# Schematic_OpenBook.net
KiCad netlist of a schematic drawn in EAGLE
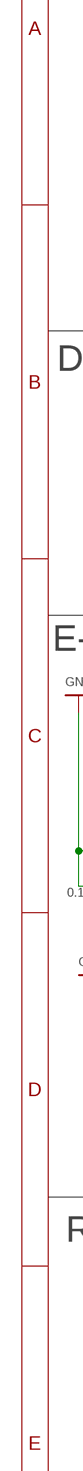
[diagram p0: schematic, sheet 1, part 1 of 2]
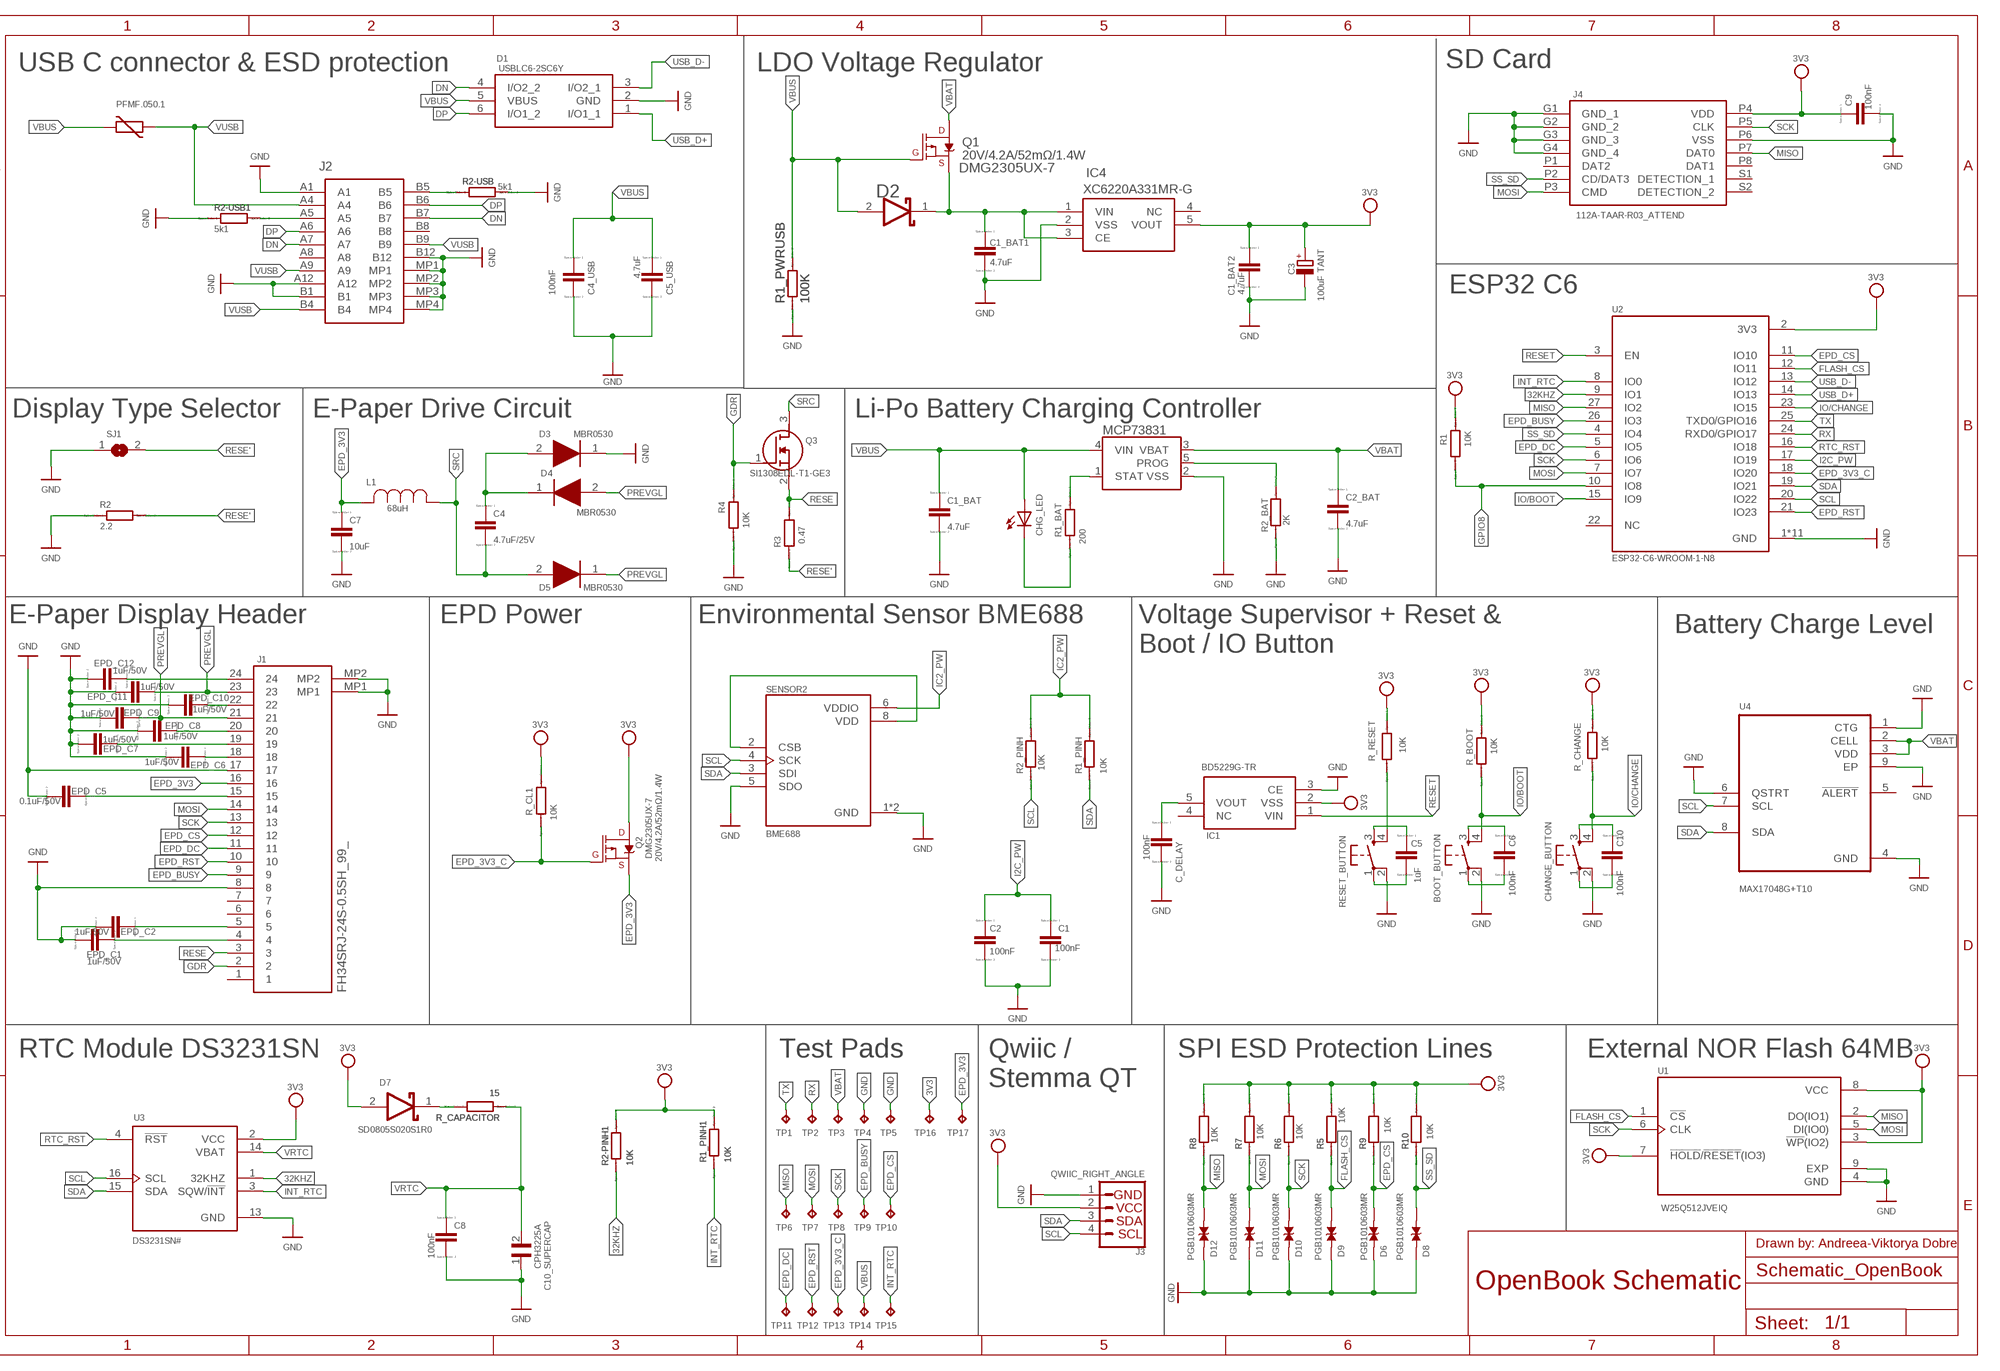
[diagram p1: schematic, sheet 1, part 2 of 2]

(export (version "E")
  (design (tool "Eeschema 10.0.6"))
  (components
    (comp (ref "BOOT_BUTTON")
      (value "BUTTON_CUSYOMV1")
      (footprint "eagle-import:MYBUTTON")
      (libsource (lib "eagle-import") (part "BUTTON_CUSYOMV1"))
    )
    (comp (ref "C1")
      (value "100nF")
      (footprint "eagle-import:ESP32_WROVER_EAGLE-LTSPICE_C0402")
      (libsource (lib "eagle-import") (part "ESP32_WROVER_EAGLE-LTSPICE_CC0402"))
    )
    (comp (ref "C1_BAT")
      (value "4.7uF")
      (footprint "eagle-import:ESP32_WROVER_EAGLE-LTSPICE_C0402")
      (libsource (lib "eagle-import") (part "ESP32_WROVER_EAGLE-LTSPICE_CC0402"))
    )
    (comp (ref "C1_BAT1")
      (value "4.7uF")
      (footprint "eagle-import:ESP32_WROVER_EAGLE-LTSPICE_C0402")
      (libsource (lib "eagle-import") (part "ESP32_WROVER_EAGLE-LTSPICE_CC0402"))
    )
    (comp (ref "C1_BAT2")
      (value "4.7uF")
      (footprint "eagle-import:ESP32_WROVER_EAGLE-LTSPICE_C0402")
      (libsource (lib "eagle-import") (part "ESP32_WROVER_EAGLE-LTSPICE_CC0402"))
    )
    (comp (ref "C2")
      (value "100nF")
      (footprint "eagle-import:ESP32_WROVER_EAGLE-LTSPICE_C0402")
      (libsource (lib "eagle-import") (part "ESP32_WROVER_EAGLE-LTSPICE_CC0402"))
    )
    (comp (ref "C2_BAT")
      (value "4.7uF")
      (footprint "eagle-import:ESP32_WROVER_EAGLE-LTSPICE_C0402")
      (libsource (lib "eagle-import") (part "ESP32_WROVER_EAGLE-LTSPICE_CC0402"))
    )
    (comp (ref "C3")
      (value "100uF TANT")
      (footprint "eagle-import:RCL_CT3528")
      (libsource (lib "eagle-import") (part "RCL_CPOL-EUCT3528"))
    )
    (comp (ref "C4")
      (value "4.7uF/25V")
      (footprint "eagle-import:ESP32_WROVER_EAGLE-LTSPICE_C0402")
      (libsource (lib "eagle-import") (part "ESP32_WROVER_EAGLE-LTSPICE_CC0402"))
    )
    (comp (ref "C4_USB")
      (value "100nF")
      (footprint "eagle-import:ESP32_WROVER_EAGLE-LTSPICE_C0402")
      (libsource (lib "eagle-import") (part "ESP32_WROVER_EAGLE-LTSPICE_CC0402"))
    )
    (comp (ref "C5")
      (value "1uF")
      (footprint "eagle-import:ESP32_WROVER_EAGLE-LTSPICE_C0402")
      (libsource (lib "eagle-import") (part "ESP32_WROVER_EAGLE-LTSPICE_CC0402"))
    )
    (comp (ref "C5_USB")
      (value "4.7uF")
      (footprint "eagle-import:ESP32_WROVER_EAGLE-LTSPICE_C0402")
      (libsource (lib "eagle-import") (part "ESP32_WROVER_EAGLE-LTSPICE_CC0402"))
    )
    (comp (ref "C6")
      (value "100nF")
      (footprint "eagle-import:ESP32_WROVER_EAGLE-LTSPICE_C0402")
      (libsource (lib "eagle-import") (part "ESP32_WROVER_EAGLE-LTSPICE_CC0402"))
    )
    (comp (ref "C7")
      (value "10uF")
      (footprint "eagle-import:ESP32_WROVER_EAGLE-LTSPICE_C0402")
      (libsource (lib "eagle-import") (part "ESP32_WROVER_EAGLE-LTSPICE_CC0402"))
    )
    (comp (ref "C8")
      (value "100nF")
      (footprint "eagle-import:ESP32_WROVER_EAGLE-LTSPICE_C0402")
      (libsource (lib "eagle-import") (part "ESP32_WROVER_EAGLE-LTSPICE_CC0402"))
    )
    (comp (ref "C9")
      (value "100nF")
      (footprint "eagle-import:ESP32_WROVER_EAGLE-LTSPICE_C0402")
      (libsource (lib "eagle-import") (part "ESP32_WROVER_EAGLE-LTSPICE_CC0402"))
    )
    (comp (ref "C10")
      (value "100nF")
      (footprint "eagle-import:ESP32_WROVER_EAGLE-LTSPICE_C0402")
      (libsource (lib "eagle-import") (part "ESP32_WROVER_EAGLE-LTSPICE_CC0402"))
    )
    (comp (ref "C10_SUPERCAP")
      (value "CPH3225A")
      (footprint "eagle-import:CAPCP3225X100N")
      (fields (field (name "MF") "Seiko Instruments"))
      (libsource (lib "eagle-import") (part "CPH3225A"))
    )
    (comp (ref "CHANGE_BUTTON")
      (value "BUTTON_CUSYOMV1")
      (footprint "eagle-import:MYBUTTON")
      (libsource (lib "eagle-import") (part "BUTTON_CUSYOMV1"))
    )
    (comp (ref "CHG_LED")
      (value "ADAFRUIT_LEDCHIP-LED0603")
      (footprint "eagle-import:ADAFRUIT_CHIP-LED0603")
      (libsource (lib "eagle-import") (part "ADAFRUIT_LEDCHIP-LED0603"))
    )
    (comp (ref "C_DELAY")
      (value "100nF")
      (footprint "eagle-import:ESP32_WROVER_EAGLE-LTSPICE_C0402")
      (libsource (lib "eagle-import") (part "ESP32_WROVER_EAGLE-LTSPICE_CC0402"))
    )
    (comp (ref "D1")
      (value "USBLC6-2SC6Y")
      (footprint "eagle-import:SOT95P280X145-6N")
      (fields (field (name "MF") "STMicroelectronics"))
      (libsource (lib "eagle-import") (part "USBLC6-2SC6Y"))
    )
    (comp (ref "D2")
      (value "ESP32_WROVER_AVX---SD0805S020S1R0_AVX_SD0805S020S1R0_0_0AVX_SD0805S020S1R0_0_0")
      (footprint "eagle-import:ESP32_WROVER_AVX---SD0805S020S1R0_AVX_SD0805S020S1R0_0")
      (fields
        (field (name "DIGIKEY_PART_NUMBER") "478-7800-1-ND")
        (field (name "MF") "AVX")
        (field (name "MOUSER_PART_NUMBER") "581-SD0805S020S1R0")
      )
      (libsource (lib "eagle-import") (part "ESP32_WROVER_AVX---SD0805S020S1R0_AVX_SD0805S020S1R0_0_0AVX_SD0805S020S1R0_0_0"))
    )
    (comp (ref "D3")
      (value "MBR0530")
      (footprint "eagle-import:SOD3716X135N")
      (fields (field (name "MF") "ON Semiconductor"))
      (libsource (lib "eagle-import") (part "MBR0530"))
    )
    (comp (ref "D4")
      (value "MBR0530")
      (footprint "eagle-import:SOD3716X135N")
      (fields (field (name "MF") "ON Semiconductor"))
      (libsource (lib "eagle-import") (part "MBR0530"))
    )
    (comp (ref "D5")
      (value "MBR0530")
      (footprint "eagle-import:SOD3716X135N")
      (fields (field (name "MF") "ON Semiconductor"))
      (libsource (lib "eagle-import") (part "MBR0530"))
    )
    (comp (ref "D6")
      (value "PGB1010603MR")
      (footprint "eagle-import:DIOC1608X36N")
      (fields (field (name "MF") "Littelfuse Inc."))
      (libsource (lib "eagle-import") (part "PGB1010603MR"))
    )
    (comp (ref "D7")
      (value "ESP32_WROVER_AVX---SD0805S020S1R0_AVX_SD0805S020S1R0_0_0AVX_SD0805S020S1R0_0_0")
      (footprint "eagle-import:ESP32_WROVER_AVX---SD0805S020S1R0_AVX_SD0805S020S1R0_0")
      (fields
        (field (name "DIGIKEY_PART_NUMBER") "478-7800-1-ND")
        (field (name "MF") "AVX")
        (field (name "MOUSER_PART_NUMBER") "581-SD0805S020S1R0")
      )
      (libsource (lib "eagle-import") (part "ESP32_WROVER_AVX---SD0805S020S1R0_AVX_SD0805S020S1R0_0_0AVX_SD0805S020S1R0_0_0"))
    )
    (comp (ref "D8")
      (value "PGB1010603MR")
      (footprint "eagle-import:DIOC1608X36N")
      (fields (field (name "MF") "Littelfuse Inc."))
      (libsource (lib "eagle-import") (part "PGB1010603MR"))
    )
    (comp (ref "D9")
      (value "PGB1010603MR")
      (footprint "eagle-import:DIOC1608X36N")
      (fields (field (name "MF") "Littelfuse Inc."))
      (libsource (lib "eagle-import") (part "PGB1010603MR"))
    )
    (comp (ref "D10")
      (value "PGB1010603MR")
      (footprint "eagle-import:DIOC1608X36N")
      (fields (field (name "MF") "Littelfuse Inc."))
      (libsource (lib "eagle-import") (part "PGB1010603MR"))
    )
    (comp (ref "D11")
      (value "PGB1010603MR")
      (footprint "eagle-import:DIOC1608X36N")
      (fields (field (name "MF") "Littelfuse Inc."))
      (libsource (lib "eagle-import") (part "PGB1010603MR"))
    )
    (comp (ref "D12")
      (value "PGB1010603MR")
      (footprint "eagle-import:DIOC1608X36N")
      (fields (field (name "MF") "Littelfuse Inc."))
      (libsource (lib "eagle-import") (part "PGB1010603MR"))
    )
    (comp (ref "EPD_C1")
      (value "1uF/50V")
      (footprint "eagle-import:ESP32_WROVER_EAGLE-LTSPICE_C0402")
      (libsource (lib "eagle-import") (part "ESP32_WROVER_EAGLE-LTSPICE_CC0402"))
    )
    (comp (ref "EPD_C2")
      (value "1uF/50V")
      (footprint "eagle-import:ESP32_WROVER_EAGLE-LTSPICE_C0402")
      (libsource (lib "eagle-import") (part "ESP32_WROVER_EAGLE-LTSPICE_CC0402"))
    )
    (comp (ref "EPD_C5")
      (value "0.1uF/50V")
      (footprint "eagle-import:ESP32_WROVER_EAGLE-LTSPICE_C0402")
      (libsource (lib "eagle-import") (part "ESP32_WROVER_EAGLE-LTSPICE_CC0402"))
    )
    (comp (ref "EPD_C6")
      (value "1uF/50V")
      (footprint "eagle-import:ESP32_WROVER_EAGLE-LTSPICE_C0402")
      (libsource (lib "eagle-import") (part "ESP32_WROVER_EAGLE-LTSPICE_CC0402"))
    )
    (comp (ref "EPD_C7")
      (value "1uF/50V")
      (footprint "eagle-import:ESP32_WROVER_EAGLE-LTSPICE_C0402")
      (libsource (lib "eagle-import") (part "ESP32_WROVER_EAGLE-LTSPICE_CC0402"))
    )
    (comp (ref "EPD_C8")
      (value "1uF/50V")
      (footprint "eagle-import:ESP32_WROVER_EAGLE-LTSPICE_C0402")
      (libsource (lib "eagle-import") (part "ESP32_WROVER_EAGLE-LTSPICE_CC0402"))
    )
    (comp (ref "EPD_C9")
      (value "1uF/50V")
      (footprint "eagle-import:ESP32_WROVER_EAGLE-LTSPICE_C0402")
      (libsource (lib "eagle-import") (part "ESP32_WROVER_EAGLE-LTSPICE_CC0402"))
    )
    (comp (ref "EPD_C10")
      (value "1uF/50V")
      (footprint "eagle-import:ESP32_WROVER_EAGLE-LTSPICE_C0402")
      (libsource (lib "eagle-import") (part "ESP32_WROVER_EAGLE-LTSPICE_CC0402"))
    )
    (comp (ref "EPD_C11")
      (value "1uF/50V")
      (footprint "eagle-import:ESP32_WROVER_EAGLE-LTSPICE_C0402")
      (libsource (lib "eagle-import") (part "ESP32_WROVER_EAGLE-LTSPICE_CC0402"))
    )
    (comp (ref "EPD_C12")
      (value "1uF/50V")
      (footprint "eagle-import:ESP32_WROVER_EAGLE-LTSPICE_C0402")
      (libsource (lib "eagle-import") (part "ESP32_WROVER_EAGLE-LTSPICE_CC0402"))
    )
    (comp (ref "IC1")
      (value "XC6220A331MR-G")
      (footprint "eagle-import:SOT95P280X120-5N")
      (fields
        (field (name "MANUFACTURER_PART_NUMBER") "XC6220A331MR-G")
        (field (name "MOUSER_PART_NUMBER") "865-XC6220A331MR-G")
        (field (name "MANUFACTURER_PART_NUMBER_1") "BD5229G-TR")
      )
      (libsource (lib "eagle-import") (part "XC6220A331MR-G"))
    )
    (comp (ref "IC4")
      (value "XC6220A331MR-G")
      (footprint "eagle-import:SOT95P280X120-5N")
      (fields (field (name "MOUSER_PART_NUMBER") "865-XC6220A331MR-G"))
      (libsource (lib "eagle-import") (part "XC6220A331MR-G"))
    )
    (comp (ref "J1")
      (value "FH34SRJ-24S-0.5SH_99_")
      (footprint "eagle-import:FH34SRJ24S05SH99")
      (fields
        (field (name "MANUFACTURER_PART_NUMBER") "FH34SRJ-24S-0.5SH(99)")
        (field (name "MOUSER_PART_NUMBER") "798-FH34SRJ24S05SH99")
      )
      (libsource (lib "eagle-import") (part "FH34SRJ-24S-0.5SH_99_"))
    )
    (comp (ref "J2")
      (value "SAMACSYS_PARTS_USB4110-GF-A")
      (footprint "eagle-import:SAMACSYS_PARTS_USB4110GFA")
      (fields
        (field (name "MANUFACTURER_PART_NUMBER") "USB4110-GF-A")
        (field (name "MOUSER_PART_NUMBER") "640-USB4110-GF-A")
      )
      (libsource (lib "eagle-import") (part "SAMACSYS_PARTS_USB4110-GF-A"))
    )
    (comp (ref "J3")
      (value "QWIIC_RIGHT_ANGLE")
      (footprint "eagle-import:JST04_1MM_RA")
      (libsource (lib "eagle-import") (part "QWIIC_CONNECTORJS-1MM"))
    )
    (comp (ref "J4")
      (value "112A-TAAR-R03_ATTEND")
      (footprint "eagle-import:112ATAARR03ATTEND")
      (fields (field (name "MANUFACTURER_PART_NUMBER") "112A-TAAR-R03 ATTEND"))
      (libsource (lib "eagle-import") (part "112A-TAAR-R03_ATTEND"))
    )
    (comp (ref "L1")
      (value "68uH")
      (footprint "eagle-import:IND_4828-WE-TPC_WRE")
      (fields
        (field (name "MANUFACTURER_PART_NUMBER") "744043680")
        (field (name "COPYRIGHT") "Copyright (C) 2024 Ultra Librarian. All rights reserved.")
      )
      (libsource (lib "eagle-import") (part "744043680IND_4828-WE-TPC_WRE"))
    )
    (comp (ref "MCP73831")
      (value "ESP32_WROVER_SPARKFUN-IC-POWER_MCP73831")
      (footprint "eagle-import:ESP32_WROVER_SPARKFUN-IC-POWER_SOT23-5")
      (libsource (lib "eagle-import") (part "ESP32_WROVER_SPARKFUN-IC-POWER_MCP73831"))
    )
    (comp (ref "PFMF.050.1")
      (value "ESP32C6_VARISTORCN1812")
      (footprint "eagle-import:ESP32C6_VARISTOR_CT_CN1812")
      (libsource (lib "eagle-import") (part "ESP32C6_VARISTORCN1812"))
    )
    (comp (ref "Q1")
      (value "20V/4.2A/52mΩ/1.4W")
      (footprint "eagle-import:ESP32_WROVER_SPARKFUN-DISCRETESEMI_SOT23-3")
      (libsource (lib "eagle-import") (part "ESP32_WROVER_SPARKFUN-DISCRETESEMI_MOSFET_PCH-DMG2305UX-7"))
    )
    (comp (ref "Q2")
      (value "20V/4.2A/52mΩ/1.4W")
      (footprint "eagle-import:ESP32_WROVER_SPARKFUN-DISCRETESEMI_SOT23-3")
      (libsource (lib "eagle-import") (part "ESP32_WROVER_SPARKFUN-DISCRETESEMI_MOSFET_PCH-DMG2305UX-7"))
    )
    (comp (ref "Q3")
      (value "SI1308EDL-T1-GE3")
      (footprint "eagle-import:SOT65P210X110-3N")
      (fields (field (name "MF") "Vishay Siliconix"))
      (libsource (lib "eagle-import") (part "SI1308EDL-T1-GE3"))
    )
    (comp (ref "R1")
      (value "10K")
      (footprint "eagle-import:ESP32_WROVER_EAGLE-LTSPICE_R0402")
      (libsource (lib "eagle-import") (part "ESP32_WROVER_EAGLE-LTSPICE_RR0402"))
    )
    (comp (ref "R1_BAT")
      (value "200")
      (footprint "eagle-import:ESP32_WROVER_EAGLE-LTSPICE_R0402")
      (libsource (lib "eagle-import") (part "ESP32_WROVER_EAGLE-LTSPICE_RR0402"))
    )
    (comp (ref "R1_PINH")
      (value "10K")
      (footprint "eagle-import:ESP32_WROVER_EAGLE-LTSPICE_R0402")
      (libsource (lib "eagle-import") (part "ESP32_WROVER_EAGLE-LTSPICE_RR0402"))
    )
    (comp (ref "R1_PINH1")
      (value "10K")
      (footprint "eagle-import:ESP32_WROVER_EAGLE-LTSPICE_R0402")
      (libsource (lib "eagle-import") (part "ESP32_WROVER_EAGLE-LTSPICE_RR0402"))
    )
    (comp (ref "R1_PWRUSB")
      (value "100K")
      (footprint "eagle-import:ESP32_WROVER_EAGLE-LTSPICE_R0402")
      (libsource (lib "eagle-import") (part "ESP32_WROVER_EAGLE-LTSPICE_RR0402"))
    )
    (comp (ref "R2")
      (value "2.2")
      (footprint "eagle-import:ESP32_WROVER_EAGLE-LTSPICE_R0402")
      (libsource (lib "eagle-import") (part "ESP32_WROVER_EAGLE-LTSPICE_RR0402"))
    )
    (comp (ref "R2-PINH1")
      (value "10K")
      (footprint "eagle-import:ESP32_WROVER_EAGLE-LTSPICE_R0402")
      (libsource (lib "eagle-import") (part "ESP32_WROVER_EAGLE-LTSPICE_RR0402"))
    )
    (comp (ref "R2-USB")
      (value "5k1")
      (footprint "eagle-import:ESP32_WROVER_EAGLE-LTSPICE_R0402")
      (libsource (lib "eagle-import") (part "ESP32_WROVER_EAGLE-LTSPICE_RR0402"))
    )
    (comp (ref "R2-USB1")
      (value "5k1")
      (footprint "eagle-import:ESP32_WROVER_EAGLE-LTSPICE_R0402")
      (libsource (lib "eagle-import") (part "ESP32_WROVER_EAGLE-LTSPICE_RR0402"))
    )
    (comp (ref "R2_BAT")
      (value "2K")
      (footprint "eagle-import:ESP32_WROVER_EAGLE-LTSPICE_R0402")
      (libsource (lib "eagle-import") (part "ESP32_WROVER_EAGLE-LTSPICE_RR0402"))
    )
    (comp (ref "R2_PINH")
      (value "10K")
      (footprint "eagle-import:ESP32_WROVER_EAGLE-LTSPICE_R0402")
      (libsource (lib "eagle-import") (part "ESP32_WROVER_EAGLE-LTSPICE_RR0402"))
    )
    (comp (ref "R3")
      (value "0.47")
      (footprint "eagle-import:ESP32_WROVER_EAGLE-LTSPICE_R0402")
      (libsource (lib "eagle-import") (part "ESP32_WROVER_EAGLE-LTSPICE_RR0402"))
    )
    (comp (ref "R4")
      (value "10K")
      (footprint "eagle-import:ESP32_WROVER_EAGLE-LTSPICE_R0402")
      (libsource (lib "eagle-import") (part "ESP32_WROVER_EAGLE-LTSPICE_RR0402"))
    )
    (comp (ref "R5")
      (value "10K")
      (footprint "eagle-import:ESP32_WROVER_EAGLE-LTSPICE_R0402")
      (libsource (lib "eagle-import") (part "ESP32_WROVER_EAGLE-LTSPICE_RR0402"))
    )
    (comp (ref "R6")
      (value "10K")
      (footprint "eagle-import:ESP32_WROVER_EAGLE-LTSPICE_R0402")
      (libsource (lib "eagle-import") (part "ESP32_WROVER_EAGLE-LTSPICE_RR0402"))
    )
    (comp (ref "R7")
      (value "10K")
      (footprint "eagle-import:ESP32_WROVER_EAGLE-LTSPICE_R0402")
      (libsource (lib "eagle-import") (part "ESP32_WROVER_EAGLE-LTSPICE_RR0402"))
    )
    (comp (ref "R8")
      (value "10K")
      (footprint "eagle-import:ESP32_WROVER_EAGLE-LTSPICE_R0402")
      (libsource (lib "eagle-import") (part "ESP32_WROVER_EAGLE-LTSPICE_RR0402"))
    )
    (comp (ref "R9")
      (value "10K")
      (footprint "eagle-import:ESP32_WROVER_EAGLE-LTSPICE_R0402")
      (libsource (lib "eagle-import") (part "ESP32_WROVER_EAGLE-LTSPICE_RR0402"))
    )
    (comp (ref "R10")
      (value "10K")
      (footprint "eagle-import:ESP32_WROVER_EAGLE-LTSPICE_R0402")
      (libsource (lib "eagle-import") (part "ESP32_WROVER_EAGLE-LTSPICE_RR0402"))
    )
    (comp (ref "RESET_BUTTON")
      (value "BUTTON_CUSYOMV1")
      (footprint "eagle-import:MYBUTTON")
      (libsource (lib "eagle-import") (part "BUTTON_CUSYOMV1"))
    )
    (comp (ref "R_BOOT")
      (value "10K")
      (footprint "eagle-import:ESP32_WROVER_EAGLE-LTSPICE_R0402")
      (libsource (lib "eagle-import") (part "ESP32_WROVER_EAGLE-LTSPICE_RR0402"))
    )
    (comp (ref "R_CAPACITOR")
      (value "15")
      (footprint "eagle-import:ESP32_WROVER_EAGLE-LTSPICE_R0402")
      (libsource (lib "eagle-import") (part "ESP32_WROVER_EAGLE-LTSPICE_RR0402"))
    )
    (comp (ref "R_CHANGE")
      (value "10K")
      (footprint "eagle-import:ESP32_WROVER_EAGLE-LTSPICE_R0402")
      (libsource (lib "eagle-import") (part "ESP32_WROVER_EAGLE-LTSPICE_RR0402"))
    )
    (comp (ref "R_CL1")
      (value "10K")
      (footprint "eagle-import:ESP32_WROVER_EAGLE-LTSPICE_R0402")
      (libsource (lib "eagle-import") (part "ESP32_WROVER_EAGLE-LTSPICE_RR0402"))
    )
    (comp (ref "R_RESET")
      (value "10K")
      (footprint "eagle-import:ESP32_WROVER_EAGLE-LTSPICE_R0402")
      (libsource (lib "eagle-import") (part "ESP32_WROVER_EAGLE-LTSPICE_RR0402"))
    )
    (comp (ref "SENSOR2")
      (value "BME688")
      (footprint "eagle-import:ESP32_WROVER_BME680_PSON80P300X300X100-8N")
      (fields (field (name "MF") "Bosch Sensortec") (field (name "MP") "BME680"))
      (libsource (lib "eagle-import") (part "ESP32_WROVER_BME680_BME680"))
    )
    (comp (ref "SJ1") (value "SJ") (footprint "eagle-import:SJ") (libsource (lib "eagle-import") (part "SJ")))
    (comp (ref "TP1")
      (value "TPTP20R")
      (footprint "eagle-import:TP20R")
      (libsource (lib "eagle-import") (part "TPTP20R"))
    )
    (comp (ref "TP2")
      (value "TPTP20R")
      (footprint "eagle-import:TP20R")
      (libsource (lib "eagle-import") (part "TPTP20R"))
    )
    (comp (ref "TP3")
      (value "TPTP20R")
      (footprint "eagle-import:TP20R")
      (libsource (lib "eagle-import") (part "TPTP20R"))
    )
    (comp (ref "TP4")
      (value "TPTP20R")
      (footprint "eagle-import:TP20R")
      (libsource (lib "eagle-import") (part "TPTP20R"))
    )
    (comp (ref "TP5")
      (value "TPTP20R")
      (footprint "eagle-import:TP20R")
      (libsource (lib "eagle-import") (part "TPTP20R"))
    )
    (comp (ref "TP6")
      (value "TPTP20R")
      (footprint "eagle-import:TP20R")
      (libsource (lib "eagle-import") (part "TPTP20R"))
    )
    (comp (ref "TP7")
      (value "TPTP20R")
      (footprint "eagle-import:TP20R")
      (libsource (lib "eagle-import") (part "TPTP20R"))
    )
    (comp (ref "TP8")
      (value "TPTP20R")
      (footprint "eagle-import:TP20R")
      (libsource (lib "eagle-import") (part "TPTP20R"))
    )
    (comp (ref "TP9")
      (value "TPTP20R")
      (footprint "eagle-import:TP20R")
      (libsource (lib "eagle-import") (part "TPTP20R"))
    )
    (comp (ref "TP10")
      (value "TPTP20R")
      (footprint "eagle-import:TP20R")
      (libsource (lib "eagle-import") (part "TPTP20R"))
    )
    (comp (ref "TP11")
      (value "TPTP20R")
      (footprint "eagle-import:TP20R")
      (libsource (lib "eagle-import") (part "TPTP20R"))
    )
    (comp (ref "TP12")
      (value "TPTP20R")
      (footprint "eagle-import:TP20R")
      (libsource (lib "eagle-import") (part "TPTP20R"))
    )
    (comp (ref "TP13")
      (value "TPTP20R")
      (footprint "eagle-import:TP20R")
      (libsource (lib "eagle-import") (part "TPTP20R"))
    )
    (comp (ref "TP14")
      (value "TPTP20R")
      (footprint "eagle-import:TP20R")
      (libsource (lib "eagle-import") (part "TPTP20R"))
    )
    (comp (ref "TP15")
      (value "TPTP20R")
      (footprint "eagle-import:TP20R")
      (libsource (lib "eagle-import") (part "TPTP20R"))
    )
    (comp (ref "TP16")
      (value "TPTP20R")
      (footprint "eagle-import:TP20R")
      (libsource (lib "eagle-import") (part "TPTP20R"))
    )
    (comp (ref "TP17")
      (value "TPTP20R")
      (footprint "eagle-import:TP20R")
      (libsource (lib "eagle-import") (part "TPTP20R"))
    )
    (comp (ref "U1")
      (value "W25Q512JVEIQ")
      (footprint "eagle-import:SON127P600X800X80-9N")
      (fields (field (name "MF") "Winbond Electronics"))
      (libsource (lib "eagle-import") (part "W25Q512JVEIQ"))
    )
    (comp (ref "U2")
      (value "ESP32-C6-WROOM-1-N8")
      (footprint "eagle-import:XCVR_ESP32-C6-WROOM-1-N8")
      (fields (field (name "MF") "Espressif Systems"))
      (libsource (lib "eagle-import") (part "ESP32-C6-WROOM-1-N8"))
    )
    (comp (ref "U3")
      (value "DS3231SN#")
      (footprint "eagle-import:SOIC127P1032X265-16N")
      (fields (field (name "MF") "Analog Devices"))
      (libsource (lib "eagle-import") (part "DS3231SN#"))
    )
    (comp (ref "U4")
      (value "MAX17048G+T10")
      (footprint "eagle-import:SON50P200X200X80-9N")
      (fields (field (name "MF") "Analog Devices"))
      (libsource (lib "eagle-import") (part "MAX17048G+T10"))
    )
  )
  (nets
    (net (code "1") (name "3V3") (class "Default")
      (node (ref "C1_BAT2") (pin "1") (pinfunction "1_1") (pintype "passive"))
      (node (ref "C3") (pin "+") (pinfunction "+_+") (pintype "passive"))
      (node (ref "C9") (pin "1") (pinfunction "1_1") (pintype "passive"))
      (node (ref "D7") (pin "2") (pinfunction "ANODE_2") (pintype "bidirectional"))
      (node (ref "IC1") (pin "2") (pinfunction "VSS_2") (pintype "bidirectional"))
      (node (ref "IC4") (pin "5") (pinfunction "VOUT_5") (pintype "bidirectional"))
      (node (ref "J3") (pin "2") (pinfunction "2_2") (pintype "power_in"))
      (node (ref "J4") (pin "P4") (pinfunction "VDD_P4") (pintype "bidirectional"))
      (node (ref "Q2") (pin "3") (pinfunction "D_3") (pintype "bidirectional"))
      (node (ref "R1") (pin "1") (pinfunction "1_1") (pintype "passive"))
      (node (ref "R10") (pin "2") (pinfunction "2_2") (pintype "passive"))
      (node (ref "R1_PINH1") (pin "2") (pinfunction "2_2") (pintype "passive"))
      (node (ref "R2-PINH1") (pin "2") (pinfunction "2_2") (pintype "passive"))
      (node (ref "R5") (pin "2") (pinfunction "2_2") (pintype "passive"))
      (node (ref "R6") (pin "2") (pinfunction "2_2") (pintype "passive"))
      (node (ref "R7") (pin "2") (pinfunction "2_2") (pintype "passive"))
      (node (ref "R8") (pin "2") (pinfunction "2_2") (pintype "passive"))
      (node (ref "R9") (pin "2") (pinfunction "2_2") (pintype "passive"))
      (node (ref "R_BOOT") (pin "1") (pinfunction "1_1") (pintype "passive"))
      (node (ref "R_CHANGE") (pin "1") (pinfunction "1_1") (pintype "passive"))
      (node (ref "R_CL1") (pin "1") (pinfunction "1_1") (pintype "passive"))
      (node (ref "R_RESET") (pin "1") (pinfunction "1_1") (pintype "passive"))
      (node (ref "TP16") (pin "TP") (pinfunction "TP_TP") (pintype "input"))
      (node (ref "U1") (pin "3") (pinfunction "~{WP}(IO2)_3") (pintype "bidirectional"))
      (node (ref "U1") (pin "7") (pinfunction "~{HOLD}/~{RESET}(IO3)_7") (pintype "bidirectional"))
      (node (ref "U1") (pin "8") (pinfunction "VCC_8") (pintype "power_in"))
      (node (ref "U2") (pin "2") (pinfunction "3V3_2") (pintype "power_in"))
      (node (ref "U3") (pin "2") (pinfunction "VCC_2") (pintype "power_in"))
    )
    (net (code "2") (name "32KHZ") (class "Default")
      (node (ref "R2-PINH1") (pin "1") (pinfunction "1_1") (pintype "passive"))
      (node (ref "U2") (pin "9") (pinfunction "IO1_9") (pintype "bidirectional"))
      (node (ref "U3") (pin "1") (pinfunction "32KHZ_1") (pintype "output"))
    )
    (net (code "3") (name "DN") (class "Default")
      (node (ref "D1") (pin "4") (pinfunction "I/O2_2_4") (pintype "bidirectional"))
      (node (ref "J2") (pin "A7") (pinfunction "A7_A7") (pintype "bidirectional"))
      (node (ref "J2") (pin "B7") (pinfunction "B7_B7") (pintype "bidirectional"))
    )
    (net (code "4") (name "DP") (class "Default")
      (node (ref "D1") (pin "6") (pinfunction "I/O1_2_6") (pintype "bidirectional"))
      (node (ref "J2") (pin "A6") (pinfunction "A6_A6") (pintype "bidirectional"))
      (node (ref "J2") (pin "B6") (pinfunction "B6_B6") (pintype "bidirectional"))
    )
    (net (code "5") (name "EPD_3V3") (class "Default")
      (node (ref "C7") (pin "1") (pinfunction "1_1") (pintype "passive"))
      (node (ref "J1") (pin "16") (pinfunction "16_16") (pintype "bidirectional"))
      (node (ref "L1") (pin "2") (pinfunction "2_2") (pintype "passive"))
      (node (ref "Q2") (pin "2") (pinfunction "S_2") (pintype "bidirectional"))
      (node (ref "TP17") (pin "TP") (pinfunction "TP_TP") (pintype "input"))
    )
    (net (code "6") (name "EPD_3V3_C") (class "Default")
      (node (ref "Q2") (pin "1") (pinfunction "G_1") (pintype "bidirectional"))
      (node (ref "R_CL1") (pin "2") (pinfunction "2_2") (pintype "passive"))
      (node (ref "TP13") (pin "TP") (pinfunction "TP_TP") (pintype "input"))
      (node (ref "U2") (pin "18") (pinfunction "IO20_18") (pintype "bidirectional"))
    )
    (net (code "7") (name "EPD_BUSY") (class "Default")
      (node (ref "J1") (pin "9") (pinfunction "9_9") (pintype "bidirectional"))
      (node (ref "TP9") (pin "TP") (pinfunction "TP_TP") (pintype "input"))
      (node (ref "U2") (pin "26") (pinfunction "IO3_26") (pintype "bidirectional"))
    )
    (net (code "8") (name "EPD_CS") (class "Default")
      (node (ref "D6") (pin "2") (pinfunction "2_2") (pintype "passive"))
      (node (ref "J1") (pin "12") (pinfunction "12_12") (pintype "bidirectional"))
      (node (ref "R9") (pin "1") (pinfunction "1_1") (pintype "passive"))
      (node (ref "TP10") (pin "TP") (pinfunction "TP_TP") (pintype "input"))
      (node (ref "U2") (pin "11") (pinfunction "IO10_11") (pintype "bidirectional"))
    )
    (net (code "9") (name "EPD_DC") (class "Default")
      (node (ref "J1") (pin "11") (pinfunction "11_11") (pintype "bidirectional"))
      (node (ref "TP11") (pin "TP") (pinfunction "TP_TP") (pintype "input"))
      (node (ref "U2") (pin "5") (pinfunction "IO5_5") (pintype "bidirectional"))
    )
    (net (code "10") (name "EPD_RST") (class "Default")
      (node (ref "J1") (pin "10") (pinfunction "10_10") (pintype "bidirectional"))
      (node (ref "TP12") (pin "TP") (pinfunction "TP_TP") (pintype "input"))
      (node (ref "U2") (pin "21") (pinfunction "IO23_21") (pintype "bidirectional"))
    )
    (net (code "11") (name "FLASH_CS") (class "Default")
      (node (ref "D9") (pin "2") (pinfunction "2_2") (pintype "passive"))
      (node (ref "R5") (pin "1") (pinfunction "1_1") (pintype "passive"))
      (node (ref "U1") (pin "1") (pinfunction "~{CS}_1") (pintype "input"))
      (node (ref "U2") (pin "12") (pinfunction "IO11_12") (pintype "bidirectional"))
    )
    (net (code "12") (name "GDR") (class "Default")
      (node (ref "J1") (pin "2") (pinfunction "2_2") (pintype "bidirectional"))
      (node (ref "Q3") (pin "1") (pinfunction "G_1") (pintype "bidirectional"))
      (node (ref "R4") (pin "1") (pinfunction "1_1") (pintype "passive"))
    )
    (net (code "13") (name "GND") (class "Default")
      (node (ref "BOOT_BUTTON") (pin "2") (pinfunction "2_2") (pintype "passive"))
      (node (ref "C1") (pin "2") (pinfunction "2_2") (pintype "passive"))
      (node (ref "C10_SUPERCAP") (pin "1") (pinfunction "1_1") (pintype "passive"))
      (node (ref "C1_BAT") (pin "2") (pinfunction "2_2") (pintype "passive"))
      (node (ref "C1_BAT1") (pin "2") (pinfunction "2_2") (pintype "passive"))
      (node (ref "C1_BAT2") (pin "2") (pinfunction "2_2") (pintype "passive"))
      (node (ref "C2") (pin "2") (pinfunction "2_2") (pintype "passive"))
      (node (ref "C2_BAT") (pin "2") (pinfunction "2_2") (pintype "passive"))
      (node (ref "C3") (pin "-") (pinfunction "-_-") (pintype "passive"))
      (node (ref "C4_USB") (pin "2") (pinfunction "2_2") (pintype "passive"))
      (node (ref "C5_USB") (pin "2") (pinfunction "2_2") (pintype "passive"))
      (node (ref "C7") (pin "2") (pinfunction "2_2") (pintype "passive"))
      (node (ref "C8") (pin "2") (pinfunction "2_2") (pintype "passive"))
      (node (ref "C9") (pin "2") (pinfunction "2_2") (pintype "passive"))
      (node (ref "CHANGE_BUTTON") (pin "2") (pinfunction "2_2") (pintype "passive"))
      (node (ref "C_DELAY") (pin "2") (pinfunction "2_2") (pintype "passive"))
      (node (ref "D1") (pin "2") (pinfunction "GND_2") (pintype "bidirectional"))
      (node (ref "D10") (pin "1") (pinfunction "1_1") (pintype "passive"))
      (node (ref "D11") (pin "1") (pinfunction "1_1") (pintype "passive"))
      (node (ref "D12") (pin "1") (pinfunction "1_1") (pintype "passive"))
      (node (ref "D3") (pin "1") (pinfunction "K_1") (pintype "bidirectional"))
      (node (ref "D6") (pin "1") (pinfunction "1_1") (pintype "passive"))
      (node (ref "D8") (pin "1") (pinfunction "1_1") (pintype "passive"))
      (node (ref "D9") (pin "1") (pinfunction "1_1") (pintype "passive"))
      (node (ref "EPD_C1") (pin "2") (pinfunction "2_2") (pintype "passive"))
      (node (ref "EPD_C10") (pin "2") (pinfunction "2_2") (pintype "passive"))
      (node (ref "EPD_C11") (pin "2") (pinfunction "2_2") (pintype "passive"))
      (node (ref "EPD_C12") (pin "2") (pinfunction "2_2") (pintype "passive"))
      (node (ref "EPD_C2") (pin "2") (pinfunction "2_2") (pintype "passive"))
      (node (ref "EPD_C5") (pin "2") (pinfunction "2_2") (pintype "passive"))
      (node (ref "EPD_C6") (pin "2") (pinfunction "2_2") (pintype "passive"))
      (node (ref "EPD_C7") (pin "2") (pinfunction "2_2") (pintype "passive"))
      (node (ref "EPD_C8") (pin "2") (pinfunction "2_2") (pintype "passive"))
      (node (ref "EPD_C9") (pin "2") (pinfunction "2_2") (pintype "passive"))
      (node (ref "IC1") (pin "3") (pinfunction "CE_3") (pintype "bidirectional"))
      (node (ref "IC4") (pin "2") (pinfunction "VSS_2") (pintype "bidirectional"))
      (node (ref "J1") (pin "17") (pinfunction "17_17") (pintype "bidirectional"))
      (node (ref "J1") (pin "8") (pinfunction "8_8") (pintype "bidirectional"))
      (node (ref "J1") (pin "MP1") (pinfunction "MP1_MP1") (pintype "bidirectional"))
      (node (ref "J1") (pin "MP2") (pinfunction "MP2_MP2") (pintype "bidirectional"))
      (node (ref "J2") (pin "A1") (pinfunction "A1_A1") (pintype "bidirectional"))
      (node (ref "J2") (pin "A12") (pinfunction "A12_A12") (pintype "bidirectional"))
      (node (ref "J2") (pin "B1") (pinfunction "B1_B1") (pintype "bidirectional"))
      (node (ref "J2") (pin "B12") (pinfunction "B12_B12") (pintype "bidirectional"))
      (node (ref "J2") (pin "MP1") (pinfunction "MP1_MP1") (pintype "bidirectional"))
      (node (ref "J2") (pin "MP2") (pinfunction "MP2_MP2") (pintype "bidirectional"))
      (node (ref "J2") (pin "MP3") (pinfunction "MP3_MP3") (pintype "bidirectional"))
      (node (ref "J2") (pin "MP4") (pinfunction "MP4_MP4") (pintype "bidirectional"))
      (node (ref "J3") (pin "1") (pinfunction "1_1") (pintype "power_in"))
      (node (ref "J4") (pin "G1") (pinfunction "GND_1_G1") (pintype "bidirectional"))
      (node (ref "J4") (pin "G2") (pinfunction "GND_2_G2") (pintype "bidirectional"))
      (node (ref "J4") (pin "G3") (pinfunction "GND_3_G3") (pintype "bidirectional"))
      (node (ref "J4") (pin "G4") (pinfunction "GND_4_G4") (pintype "bidirectional"))
      (node (ref "J4") (pin "P6") (pinfunction "VSS_P6") (pintype "bidirectional"))
      (node (ref "MCP73831") (pin "2") (pinfunction "VSS_2") (pintype "power_in"))
      (node (ref "R1_PWRUSB") (pin "1") (pinfunction "1_1") (pintype "passive"))
      (node (ref "R2") (pin "1") (pinfunction "1_1") (pintype "passive"))
      (node (ref "R2-USB") (pin "2") (pinfunction "2_2") (pintype "passive"))
      (node (ref "R2-USB1") (pin "1") (pinfunction "1_1") (pintype "passive"))
      (node (ref "R2_BAT") (pin "1") (pinfunction "1_1") (pintype "passive"))
      (node (ref "R4") (pin "2") (pinfunction "2_2") (pintype "passive"))
      (node (ref "RESET_BUTTON") (pin "2") (pinfunction "2_2") (pintype "passive"))
      (node (ref "SENSOR2") (pin "1") (pinfunction "GND_1") (pintype "power_in"))
      (node (ref "SENSOR2") (pin "5") (pinfunction "SDO_5") (pintype "bidirectional"))
      (node (ref "SENSOR2") (pin "7") (pinfunction "GND_7") (pintype "power_in"))
      (node (ref "SJ1") (pin "1") (pinfunction "1_1") (pintype "passive"))
      (node (ref "TP4") (pin "TP") (pinfunction "TP_TP") (pintype "input"))
      (node (ref "TP5") (pin "TP") (pinfunction "TP_TP") (pintype "input"))
      (node (ref "U1") (pin "4") (pinfunction "GND_4") (pintype "power_in"))
      (node (ref "U1") (pin "9") (pinfunction "EXP_9") (pintype "passive"))
      (node (ref "U2") (pin "1") (pinfunction "GND_1") (pintype "power_in"))
      (node (ref "U2") (pin "28") (pinfunction "GND_28") (pintype "power_in"))
      (node (ref "U2") (pin "29_1") (pinfunction "GND_29_1") (pintype "power_in"))
      (node (ref "U2") (pin "29_2") (pinfunction "GND_29_2") (pintype "power_in"))
      (node (ref "U2") (pin "29_3") (pinfunction "GND_29_3") (pintype "power_in"))
      (node (ref "U2") (pin "29_4") (pinfunction "GND_29_4") (pintype "power_in"))
      (node (ref "U2") (pin "29_5") (pinfunction "GND_29_5") (pintype "power_in"))
      (node (ref "U2") (pin "29_6") (pinfunction "GND_29_6") (pintype "power_in"))
      (node (ref "U2") (pin "29_7") (pinfunction "GND_29_7") (pintype "power_in"))
      (node (ref "U2") (pin "29_8") (pinfunction "GND_29_8") (pintype "power_in"))
      (node (ref "U2") (pin "29_9") (pinfunction "GND_29_9") (pintype "power_in"))
      (node (ref "U3") (pin "13") (pinfunction "GND_13") (pintype "power_in"))
      (node (ref "U4") (pin "1") (pinfunction "CTG_1") (pintype "power_in"))
      (node (ref "U4") (pin "4") (pinfunction "GND_4") (pintype "power_in"))
      (node (ref "U4") (pin "6") (pinfunction "QSTRT_6") (pintype "input"))
      (node (ref "U4") (pin "9") (pinfunction "EP_9") (pintype "power_in"))
    )
    (net (code "14") (name "GPIO8") (class "Default")
      (node (ref "R1") (pin "2") (pinfunction "2_2") (pintype "passive"))
      (node (ref "U2") (pin "10") (pinfunction "IO8_10") (pintype "bidirectional"))
    )
    (net (code "15") (name "I2C_PW") (class "Default")
      (node (ref "C1") (pin "1") (pinfunction "1_1") (pintype "passive"))
      (node (ref "C2") (pin "1") (pinfunction "1_1") (pintype "passive"))
      (node (ref "U2") (pin "17") (pinfunction "IO19_17") (pintype "bidirectional"))
    )
    (net (code "16") (name "IC2_PW") (class "Default")
      (node (ref "R1_PINH") (pin "2") (pinfunction "2_2") (pintype "passive"))
      (node (ref "R2_PINH") (pin "2") (pinfunction "2_2") (pintype "passive"))
      (node (ref "SENSOR2") (pin "6") (pinfunction "VDDIO_6") (pintype "power_in"))
    )
    (net (code "17") (name "INT_RTC") (class "Default")
      (node (ref "R1_PINH1") (pin "1") (pinfunction "1_1") (pintype "passive"))
      (node (ref "TP15") (pin "TP") (pinfunction "TP_TP") (pintype "input"))
      (node (ref "U2") (pin "8") (pinfunction "IO0_8") (pintype "bidirectional"))
      (node (ref "U3") (pin "3") (pinfunction "SQW/~{INT}_3") (pintype "output"))
    )
    (net (code "18") (name "IO{slash}BOOT") (class "Default")
      (node (ref "BOOT_BUTTON") (pin "4") (pinfunction "4_4") (pintype "passive"))
      (node (ref "R_BOOT") (pin "2") (pinfunction "2_2") (pintype "passive"))
      (node (ref "U2") (pin "15") (pinfunction "IO9_15") (pintype "bidirectional"))
    )
    (net (code "19") (name "IO{slash}CHANGE") (class "Default")
      (node (ref "CHANGE_BUTTON") (pin "4") (pinfunction "4_4") (pintype "passive"))
      (node (ref "R_CHANGE") (pin "2") (pinfunction "2_2") (pintype "passive"))
      (node (ref "U2") (pin "23") (pinfunction "IO15_23") (pintype "bidirectional"))
    )
    (net (code "20") (name "MISO") (class "Default")
      (node (ref "D12") (pin "2") (pinfunction "2_2") (pintype "passive"))
      (node (ref "J4") (pin "P7") (pinfunction "DAT0_P7") (pintype "bidirectional"))
      (node (ref "R8") (pin "1") (pinfunction "1_1") (pintype "passive"))
      (node (ref "TP6") (pin "TP") (pinfunction "TP_TP") (pintype "input"))
      (node (ref "U1") (pin "2") (pinfunction "DO(IO1)_2") (pintype "bidirectional"))
      (node (ref "U2") (pin "27") (pinfunction "IO2_27") (pintype "bidirectional"))
    )
    (net (code "21") (name "MOSI") (class "Default")
      (node (ref "D11") (pin "2") (pinfunction "2_2") (pintype "passive"))
      (node (ref "J1") (pin "14") (pinfunction "14_14") (pintype "bidirectional"))
      (node (ref "J4") (pin "P3") (pinfunction "CMD_P3") (pintype "bidirectional"))
      (node (ref "R7") (pin "1") (pinfunction "1_1") (pintype "passive"))
      (node (ref "TP7") (pin "TP") (pinfunction "TP_TP") (pintype "input"))
      (node (ref "U1") (pin "5") (pinfunction "DI(IO0)_5") (pintype "bidirectional"))
      (node (ref "U2") (pin "7") (pinfunction "IO7_7") (pintype "bidirectional"))
    )
    (net (code "22") (name "Net-(BOOT_BUTTON-Pad1)") (class "Default")
      (node (ref "BOOT_BUTTON") (pin "1") (pinfunction "1_1") (pintype "passive"))
      (node (ref "C6") (pin "2") (pinfunction "2_2") (pintype "passive"))
    )
    (net (code "23") (name "Net-(BOOT_BUTTON-Pad3)") (class "Default")
      (node (ref "BOOT_BUTTON") (pin "3") (pinfunction "3_3") (pintype "passive"))
      (node (ref "C6") (pin "1") (pinfunction "1_1") (pintype "passive"))
    )
    (net (code "24") (name "Net-(C5-Pad1)") (class "Default")
      (node (ref "C5") (pin "1") (pinfunction "1_1") (pintype "passive"))
      (node (ref "RESET_BUTTON") (pin "3") (pinfunction "3_3") (pintype "passive"))
    )
    (net (code "25") (name "Net-(C5-Pad2)") (class "Default")
      (node (ref "C5") (pin "2") (pinfunction "2_2") (pintype "passive"))
      (node (ref "RESET_BUTTON") (pin "1") (pinfunction "1_1") (pintype "passive"))
    )
    (net (code "26") (name "Net-(C10-Pad1)") (class "Default")
      (node (ref "C10") (pin "1") (pinfunction "1_1") (pintype "passive"))
      (node (ref "CHANGE_BUTTON") (pin "3") (pinfunction "3_3") (pintype "passive"))
    )
    (net (code "27") (name "Net-(C10-Pad2)") (class "Default")
      (node (ref "C10") (pin "2") (pinfunction "2_2") (pintype "passive"))
      (node (ref "CHANGE_BUTTON") (pin "1") (pinfunction "1_1") (pintype "passive"))
    )
    (net (code "28") (name "Net-(CHG_LED-PadC)") (class "Default")
      (node (ref "CHG_LED") (pin "C") (pinfunction "C_C") (pintype "passive"))
      (node (ref "R1_BAT") (pin "2") (pinfunction "2_2") (pintype "passive"))
    )
    (net (code "29") (name "Net-(D2-CATHODE)") (class "Default")
      (node (ref "C1_BAT1") (pin "1") (pinfunction "1_1") (pintype "passive"))
      (node (ref "D2") (pin "1") (pinfunction "CATHODE_1") (pintype "bidirectional"))
      (node (ref "IC4") (pin "1") (pinfunction "VIN_1") (pintype "bidirectional"))
      (node (ref "IC4") (pin "3") (pinfunction "CE_3") (pintype "bidirectional"))
      (node (ref "Q1") (pin "2") (pinfunction "S_2") (pintype "bidirectional"))
    )
    (net (code "30") (name "Net-(D3-A)") (class "Default")
      (node (ref "C4") (pin "1") (pinfunction "1_1") (pintype "passive"))
      (node (ref "D3") (pin "2") (pinfunction "A_2") (pintype "bidirectional"))
      (node (ref "D4") (pin "1") (pinfunction "K_1") (pintype "bidirectional"))
    )
    (net (code "31") (name "Net-(D7-CATHODE)") (class "Default")
      (node (ref "D7") (pin "1") (pinfunction "CATHODE_1") (pintype "bidirectional"))
      (node (ref "R_CAPACITOR") (pin "2") (pinfunction "2_2") (pintype "passive"))
    )
    (net (code "32") (name "Net-(EPD_C1-Pad1)") (class "Default")
      (node (ref "EPD_C1") (pin "1") (pinfunction "1_1") (pintype "passive"))
      (node (ref "J1") (pin "4") (pinfunction "4_4") (pintype "bidirectional"))
    )
    (net (code "33") (name "Net-(EPD_C2-Pad1)") (class "Default")
      (node (ref "EPD_C2") (pin "1") (pinfunction "1_1") (pintype "passive"))
      (node (ref "J1") (pin "5") (pinfunction "5_5") (pintype "bidirectional"))
    )
    (net (code "34") (name "Net-(EPD_C5-Pad1)") (class "Default")
      (node (ref "EPD_C5") (pin "1") (pinfunction "1_1") (pintype "passive"))
      (node (ref "J1") (pin "15") (pinfunction "15_15") (pintype "bidirectional"))
    )
    (net (code "35") (name "Net-(EPD_C6-Pad1)") (class "Default")
      (node (ref "EPD_C6") (pin "1") (pinfunction "1_1") (pintype "passive"))
      (node (ref "J1") (pin "18") (pinfunction "18_18") (pintype "bidirectional"))
    )
    (net (code "36") (name "Net-(EPD_C7-Pad1)") (class "Default")
      (node (ref "EPD_C7") (pin "1") (pinfunction "1_1") (pintype "passive"))
      (node (ref "J1") (pin "19") (pinfunction "19_19") (pintype "bidirectional"))
    )
    (net (code "37") (name "Net-(EPD_C8-Pad1)") (class "Default")
      (node (ref "EPD_C8") (pin "1") (pinfunction "1_1") (pintype "passive"))
      (node (ref "J1") (pin "20") (pinfunction "20_20") (pintype "bidirectional"))
    )
    (net (code "38") (name "Net-(EPD_C10-Pad1)") (class "Default")
      (node (ref "EPD_C10") (pin "1") (pinfunction "1_1") (pintype "passive"))
      (node (ref "J1") (pin "22") (pinfunction "22_22") (pintype "bidirectional"))
    )
    (net (code "39") (name "Net-(EPD_C12-Pad1)") (class "Default")
      (node (ref "EPD_C12") (pin "1") (pinfunction "1_1") (pintype "passive"))
      (node (ref "J1") (pin "24") (pinfunction "24_24") (pintype "bidirectional"))
    )
    (net (code "40") (name "Net-(IC1-VOUT)") (class "Default")
      (node (ref "C_DELAY") (pin "1") (pinfunction "1_1") (pintype "passive"))
      (node (ref "IC1") (pin "5") (pinfunction "VOUT_5") (pintype "bidirectional"))
    )
    (net (code "41") (name "Net-(J2-PadA5)") (class "Default")
      (node (ref "J2") (pin "A5") (pinfunction "A5_A5") (pintype "bidirectional"))
      (node (ref "R2-USB1") (pin "2") (pinfunction "2_2") (pintype "passive"))
    )
    (net (code "42") (name "Net-(J2-PadB5)") (class "Default")
      (node (ref "J2") (pin "B5") (pinfunction "B5_B5") (pintype "bidirectional"))
      (node (ref "R2-USB") (pin "1") (pinfunction "1_1") (pintype "passive"))
    )
    (net (code "43") (name "Net-(MCP73831-PROG)") (class "Default")
      (node (ref "MCP73831") (pin "5") (pinfunction "PROG_5") (pintype "input"))
      (node (ref "R2_BAT") (pin "2") (pinfunction "2_2") (pintype "passive"))
    )
    (net (code "44") (name "Net-(MCP73831-STAT)") (class "Default")
      (node (ref "MCP73831") (pin "1") (pinfunction "STAT_1") (pintype "output"))
      (node (ref "R1_BAT") (pin "1") (pinfunction "1_1") (pintype "passive"))
    )
    (net (code "45") (name "Net-(RESET_BUTTON-Pad4)") (class "Default")
      (node (ref "RESET_BUTTON") (pin "4") (pinfunction "4_4") (pintype "passive"))
      (node (ref "R_RESET") (pin "2") (pinfunction "2_2") (pintype "passive"))
    )
    (net (code "46") (name "Net-(SENSOR2-CSB)") (class "Default")
      (node (ref "SENSOR2") (pin "2") (pinfunction "CSB_2") (pintype "input"))
      (node (ref "SENSOR2") (pin "8") (pinfunction "VDD_8") (pintype "power_in"))
    )
    (net (code "47") (name "PREVGL") (class "Default")
      (node (ref "D4") (pin "2") (pinfunction "A_2") (pintype "bidirectional"))
      (node (ref "D5") (pin "1") (pinfunction "K_1") (pintype "bidirectional"))
      (node (ref "EPD_C11") (pin "1") (pinfunction "1_1") (pintype "passive"))
      (node (ref "EPD_C9") (pin "1") (pinfunction "1_1") (pintype "passive"))
      (node (ref "J1") (pin "21") (pinfunction "21_21") (pintype "bidirectional"))
      (node (ref "J1") (pin "23") (pinfunction "23_23") (pintype "bidirectional"))
    )
    (net (code "48") (name "RESE") (class "Default")
      (node (ref "J1") (pin "3") (pinfunction "3_3") (pintype "bidirectional"))
      (node (ref "Q3") (pin "2") (pinfunction "S_2") (pintype "bidirectional"))
      (node (ref "R3") (pin "1") (pinfunction "1_1") (pintype "passive"))
    )
    (net (code "49") (name "RESE'") (class "Default")
      (node (ref "R2") (pin "2") (pinfunction "2_2") (pintype "passive"))
      (node (ref "R3") (pin "2") (pinfunction "2_2") (pintype "passive"))
      (node (ref "SJ1") (pin "2") (pinfunction "2_2") (pintype "passive"))
    )
    (net (code "50") (name "RESET") (class "Default")
      (node (ref "IC1") (pin "1") (pinfunction "VIN_1") (pintype "bidirectional"))
      (node (ref "U2") (pin "3") (pinfunction "EN_3") (pintype "input"))
    )
    (net (code "51") (name "RTC_RST") (class "Default")
      (node (ref "U2") (pin "16") (pinfunction "IO18_16") (pintype "bidirectional"))
      (node (ref "U3") (pin "4") (pinfunction "~{RST}_4") (pintype "input"))
    )
    (net (code "52") (name "RX") (class "Default")
      (node (ref "TP2") (pin "TP") (pinfunction "TP_TP") (pintype "input"))
      (node (ref "U2") (pin "24") (pinfunction "RXD0/GPIO17_24") (pintype "bidirectional"))
    )
    (net (code "53") (name "SCK") (class "Default")
      (node (ref "D10") (pin "2") (pinfunction "2_2") (pintype "passive"))
      (node (ref "J1") (pin "13") (pinfunction "13_13") (pintype "bidirectional"))
      (node (ref "J4") (pin "P5") (pinfunction "CLK_P5") (pintype "bidirectional"))
      (node (ref "R6") (pin "1") (pinfunction "1_1") (pintype "passive"))
      (node (ref "TP8") (pin "TP") (pinfunction "TP_TP") (pintype "input"))
      (node (ref "U1") (pin "6") (pinfunction "CLK_6") (pintype "input"))
      (node (ref "U2") (pin "6") (pinfunction "IO6_6") (pintype "bidirectional"))
    )
    (net (code "54") (name "SCL") (class "Default")
      (node (ref "J3") (pin "4") (pinfunction "4_4") (pintype "passive"))
      (node (ref "R2_PINH") (pin "1") (pinfunction "1_1") (pintype "passive"))
      (node (ref "SENSOR2") (pin "4") (pinfunction "SCK_4") (pintype "input"))
      (node (ref "U2") (pin "20") (pinfunction "IO22_20") (pintype "bidirectional"))
      (node (ref "U3") (pin "16") (pinfunction "SCL_16") (pintype "input"))
      (node (ref "U4") (pin "7") (pinfunction "SCL_7") (pintype "input"))
    )
    (net (code "55") (name "SDA") (class "Default")
      (node (ref "J3") (pin "3") (pinfunction "3_3") (pintype "passive"))
      (node (ref "R1_PINH") (pin "1") (pinfunction "1_1") (pintype "passive"))
      (node (ref "SENSOR2") (pin "3") (pinfunction "SDI_3") (pintype "bidirectional"))
      (node (ref "U2") (pin "19") (pinfunction "IO21_19") (pintype "bidirectional"))
      (node (ref "U3") (pin "15") (pinfunction "SDA_15") (pintype "bidirectional"))
      (node (ref "U4") (pin "8") (pinfunction "SDA_8") (pintype "bidirectional"))
    )
    (net (code "56") (name "SRC") (class "Default")
      (node (ref "C4") (pin "2") (pinfunction "2_2") (pintype "passive"))
      (node (ref "D5") (pin "2") (pinfunction "A_2") (pintype "bidirectional"))
      (node (ref "L1") (pin "1") (pinfunction "1_1") (pintype "passive"))
      (node (ref "Q3") (pin "3") (pinfunction "D_3") (pintype "bidirectional"))
    )
    (net (code "57") (name "SS_SD") (class "Default")
      (node (ref "D8") (pin "2") (pinfunction "2_2") (pintype "passive"))
      (node (ref "J4") (pin "P2") (pinfunction "CD/DAT3_P2") (pintype "bidirectional"))
      (node (ref "R10") (pin "1") (pinfunction "1_1") (pintype "passive"))
      (node (ref "U2") (pin "4") (pinfunction "IO4_4") (pintype "bidirectional"))
    )
    (net (code "58") (name "TX") (class "Default")
      (node (ref "TP1") (pin "TP") (pinfunction "TP_TP") (pintype "input"))
      (node (ref "U2") (pin "25") (pinfunction "TXD0/GPIO16_25") (pintype "bidirectional"))
    )
    (net (code "59") (name "USB_D+") (class "Default")
      (node (ref "D1") (pin "1") (pinfunction "I/O1_1_1") (pintype "bidirectional"))
      (node (ref "U2") (pin "14") (pinfunction "IO13_14") (pintype "bidirectional"))
    )
    (net (code "60") (name "USB_D-") (class "Default")
      (node (ref "D1") (pin "3") (pinfunction "I/O2_1_3") (pintype "bidirectional"))
      (node (ref "U2") (pin "13") (pinfunction "IO12_13") (pintype "bidirectional"))
    )
    (net (code "61") (name "VBAT") (class "Default")
      (node (ref "C2_BAT") (pin "1") (pinfunction "1_1") (pintype "passive"))
      (node (ref "MCP73831") (pin "3") (pinfunction "VBAT_3") (pintype "power_in"))
      (node (ref "Q1") (pin "3") (pinfunction "D_3") (pintype "bidirectional"))
      (node (ref "TP3") (pin "TP") (pinfunction "TP_TP") (pintype "input"))
      (node (ref "U4") (pin "2") (pinfunction "CELL_2") (pintype "power_in"))
      (node (ref "U4") (pin "3") (pinfunction "VDD_3") (pintype "power_in"))
    )
    (net (code "62") (name "VBUS") (class "Default")
      (node (ref "C1_BAT") (pin "1") (pinfunction "1_1") (pintype "passive"))
      (node (ref "C4_USB") (pin "1") (pinfunction "1_1") (pintype "passive"))
      (node (ref "C5_USB") (pin "1") (pinfunction "1_1") (pintype "passive"))
      (node (ref "CHG_LED") (pin "A") (pinfunction "A_A") (pintype "passive"))
      (node (ref "D1") (pin "5") (pinfunction "VBUS_5") (pintype "bidirectional"))
      (node (ref "D2") (pin "2") (pinfunction "ANODE_2") (pintype "bidirectional"))
      (node (ref "MCP73831") (pin "4") (pinfunction "VIN_4") (pintype "power_in"))
      (node (ref "PFMF.050.1") (pin "2") (pinfunction "2_2") (pintype "passive"))
      (node (ref "Q1") (pin "1") (pinfunction "G_1") (pintype "bidirectional"))
      (node (ref "R1_PWRUSB") (pin "2") (pinfunction "2_2") (pintype "passive"))
      (node (ref "TP14") (pin "TP") (pinfunction "TP_TP") (pintype "input"))
    )
    (net (code "63") (name "VRTC") (class "Default")
      (node (ref "C10_SUPERCAP") (pin "2") (pinfunction "2_2") (pintype "passive"))
      (node (ref "C8") (pin "1") (pinfunction "1_1") (pintype "passive"))
      (node (ref "R_CAPACITOR") (pin "1") (pinfunction "1_1") (pintype "passive"))
      (node (ref "U3") (pin "14") (pinfunction "VBAT_14") (pintype "power_in"))
    )
    (net (code "64") (name "VUSB") (class "Default")
      (node (ref "J2") (pin "A4") (pinfunction "A4_A4") (pintype "bidirectional"))
      (node (ref "J2") (pin "A9") (pinfunction "A9_A9") (pintype "bidirectional"))
      (node (ref "J2") (pin "B4") (pinfunction "B4_B4") (pintype "bidirectional"))
      (node (ref "J2") (pin "B9") (pinfunction "B9_B9") (pintype "bidirectional"))
      (node (ref "PFMF.050.1") (pin "1") (pinfunction "1_1") (pintype "passive"))
    )
    (net (code "65") (name "unconnected-(IC1-NC-Pad4)") (class "Default")
      (node (ref "IC1") (pin "4") (pinfunction "NC_4") (pintype "no_connect"))
    )
    (net (code "66") (name "unconnected-(IC4-NC-Pad4)") (class "Default")
      (node (ref "IC4") (pin "4") (pinfunction "NC_4") (pintype "no_connect"))
    )
    (net (code "67") (name "unconnected-(J1-Pad1)") (class "Default")
      (node (ref "J1") (pin "1") (pinfunction "1_1") (pintype "bidirectional"))
    )
    (net (code "68") (name "unconnected-(J1-Pad6)") (class "Default")
      (node (ref "J1") (pin "6") (pinfunction "6_6") (pintype "bidirectional"))
    )
    (net (code "69") (name "unconnected-(J1-Pad7)") (class "Default")
      (node (ref "J1") (pin "7") (pinfunction "7_7") (pintype "bidirectional"))
    )
    (net (code "70") (name "unconnected-(J2-PadA8)") (class "Default")
      (node (ref "J2") (pin "A8") (pinfunction "A8_A8") (pintype "bidirectional"))
    )
    (net (code "71") (name "unconnected-(J2-PadB8)") (class "Default")
      (node (ref "J2") (pin "B8") (pinfunction "B8_B8") (pintype "bidirectional"))
    )
    (net (code "72") (name "unconnected-(J4-DAT1-PadP8)") (class "Default")
      (node (ref "J4") (pin "P8") (pinfunction "DAT1_P8") (pintype "bidirectional"))
    )
    (net (code "73") (name "unconnected-(J4-DAT2-PadP1)") (class "Default")
      (node (ref "J4") (pin "P1") (pinfunction "DAT2_P1") (pintype "bidirectional"))
    )
    (net (code "74") (name "unconnected-(J4-DETECTION_1-PadS1)") (class "Default")
      (node (ref "J4") (pin "S1") (pinfunction "DETECTION_1_S1") (pintype "bidirectional"))
    )
    (net (code "75") (name "unconnected-(J4-DETECTION_2-PadS2)") (class "Default")
      (node (ref "J4") (pin "S2") (pinfunction "DETECTION_2_S2") (pintype "bidirectional"))
    )
    (net (code "76") (name "unconnected-(U2-NC-Pad22)") (class "Default")
      (node (ref "U2") (pin "22") (pinfunction "NC_22") (pintype "no_connect"))
    )
    (net (code "77") (name "unconnected-(U4-~{ALERT}-Pad5)") (class "Default")
      (node (ref "U4") (pin "5") (pinfunction "~{ALERT}_5") (pintype "output"))
    )
  )
)
